# m68k_free_run.net
KiCad netlist of a schematic drawn in EAGLE
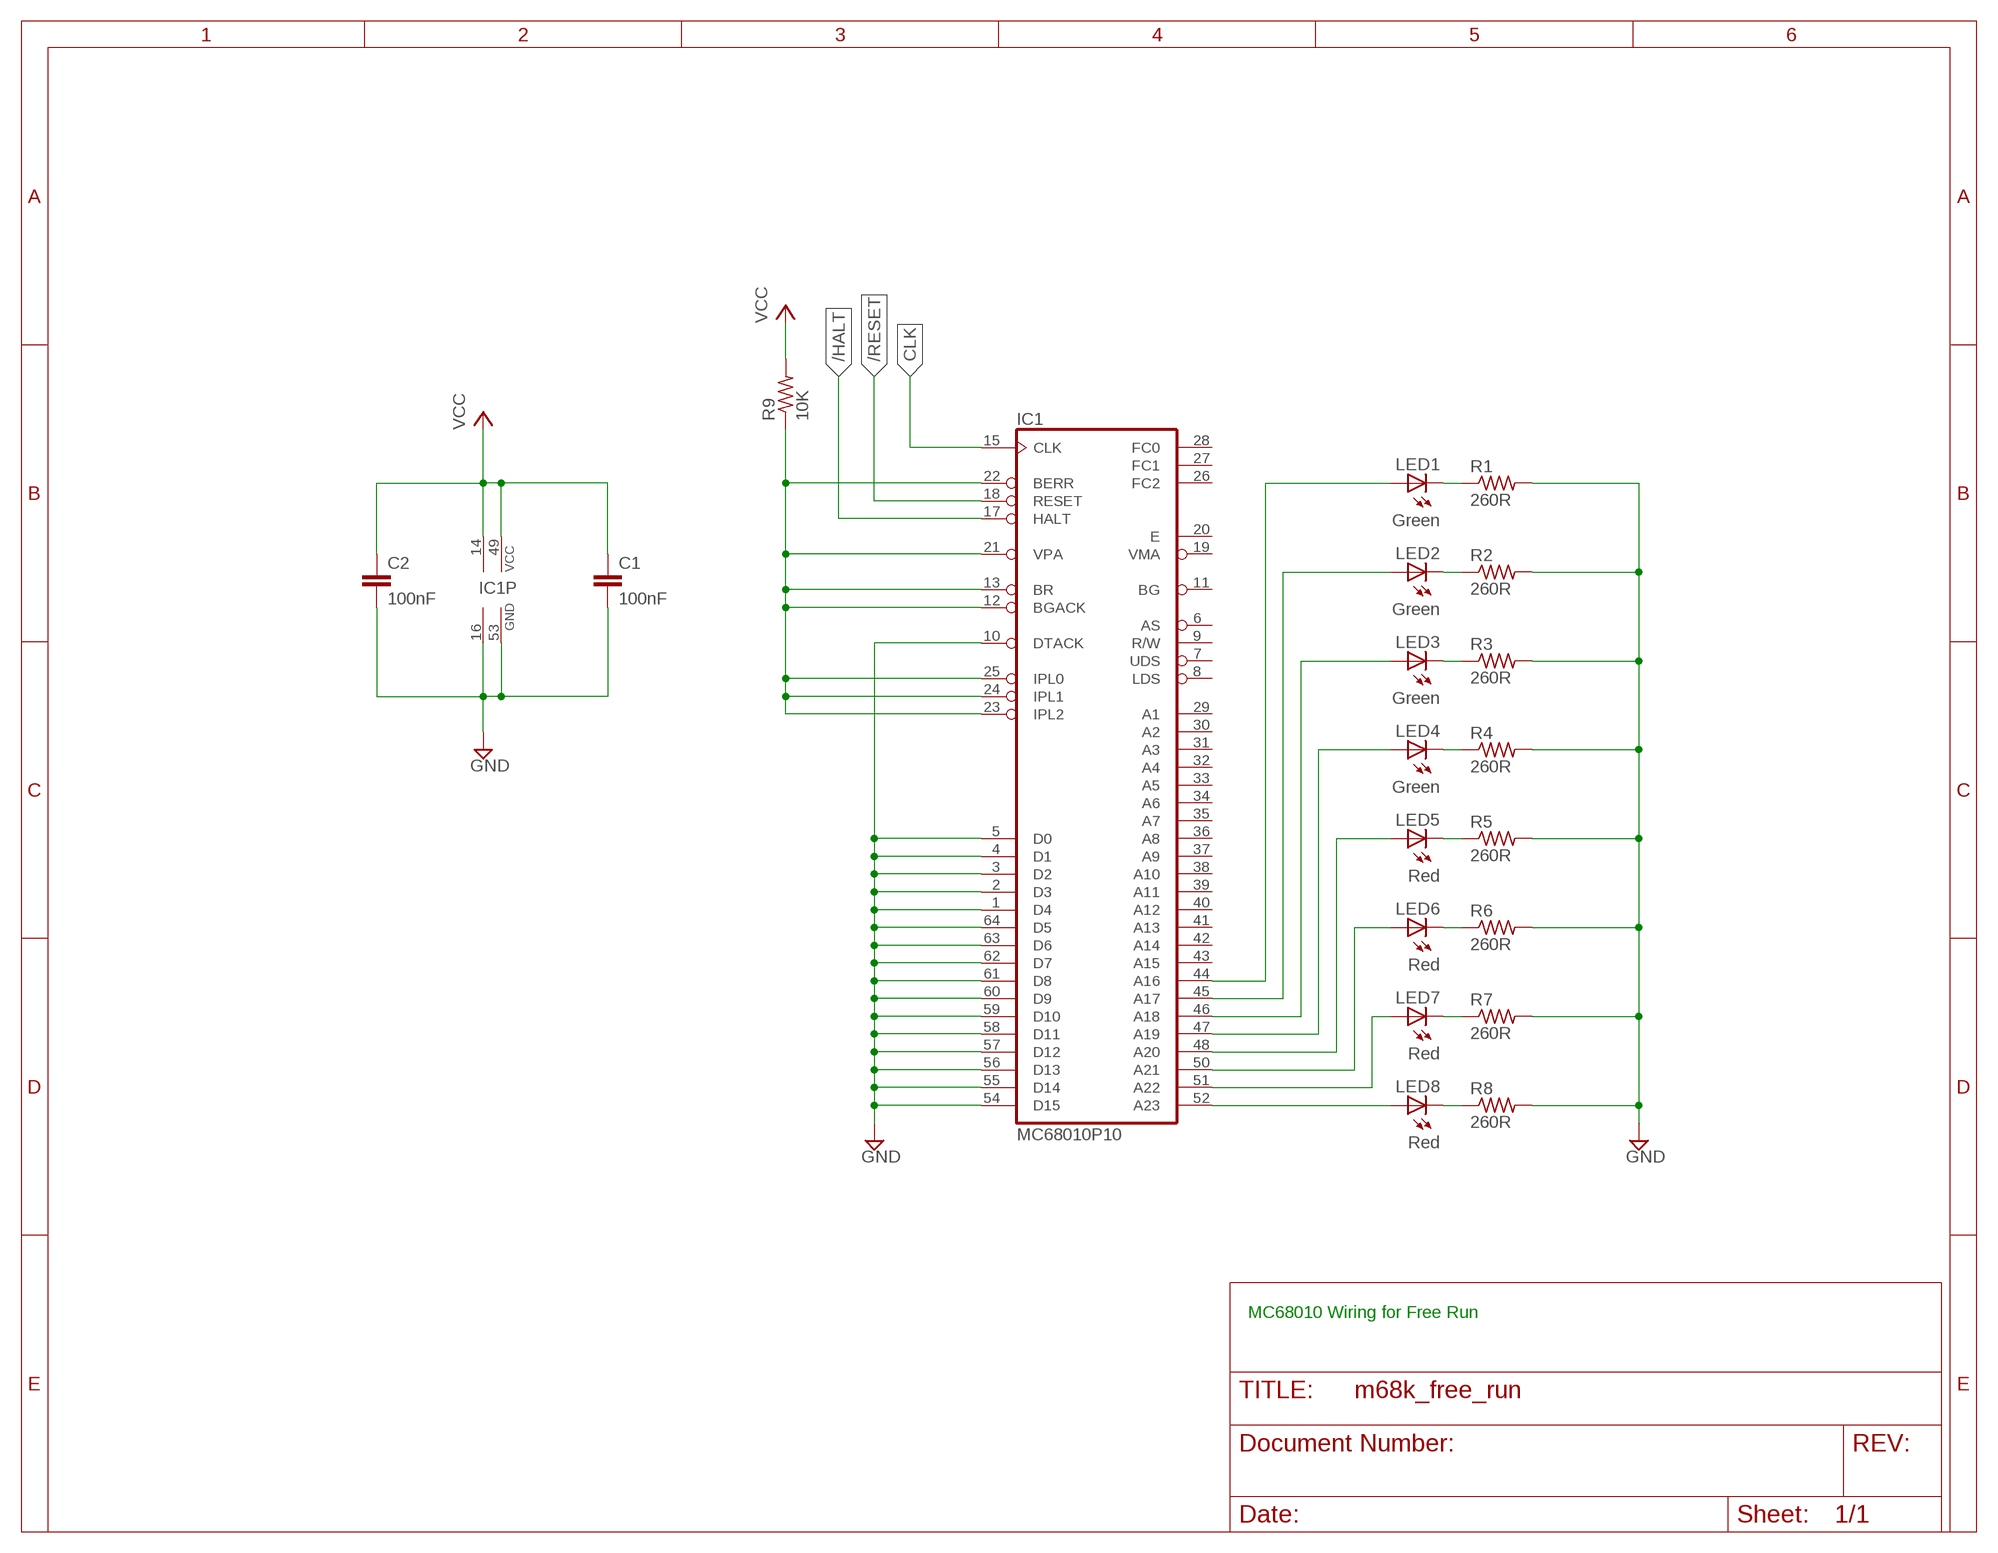
[diagram p0: schematic, sheet 1]

(export (version "E")
  (design (tool "Eeschema 10.0.6"))
  (components
    (comp (ref "C1")
      (value "100nF")
      (footprint "eagle-import:C025-024X044")
      (libsource (lib "eagle-import") (part "C-EU025-024X044"))
    )
    (comp (ref "C2")
      (value "100nF")
      (footprint "eagle-import:C025-024X044")
      (libsource (lib "eagle-import") (part "C-EU025-024X044"))
    )
    (comp (ref "IC1")
      (value "MC68010P10")
      (footprint "eagle-import:DIL64")
      (libsource (lib "eagle-import") (part "MC68000P"))
    )
    (comp (ref "LED1")
      (value "Green")
      (footprint "eagle-import:LED5MM")
      (libsource (lib "eagle-import") (part "LED5MM"))
    )
    (comp (ref "LED2")
      (value "Green")
      (footprint "eagle-import:LED5MM")
      (libsource (lib "eagle-import") (part "LED5MM"))
    )
    (comp (ref "LED3")
      (value "Green")
      (footprint "eagle-import:LED5MM")
      (libsource (lib "eagle-import") (part "LED5MM"))
    )
    (comp (ref "LED4")
      (value "Green")
      (footprint "eagle-import:LED5MM")
      (libsource (lib "eagle-import") (part "LED5MM"))
    )
    (comp (ref "LED5")
      (value "Red")
      (footprint "eagle-import:LED5MM")
      (libsource (lib "eagle-import") (part "LED5MM"))
    )
    (comp (ref "LED6")
      (value "Red")
      (footprint "eagle-import:LED5MM")
      (libsource (lib "eagle-import") (part "LED5MM"))
    )
    (comp (ref "LED7")
      (value "Red")
      (footprint "eagle-import:LED5MM")
      (libsource (lib "eagle-import") (part "LED5MM"))
    )
    (comp (ref "LED8")
      (value "Red")
      (footprint "eagle-import:LED5MM")
      (libsource (lib "eagle-import") (part "LED5MM"))
    )
    (comp (ref "R1")
      (value "260R")
      (footprint "eagle-import:0207_10")
      (libsource (lib "eagle-import") (part "R-US_0207/10"))
    )
    (comp (ref "R2")
      (value "260R")
      (footprint "eagle-import:0207_10")
      (libsource (lib "eagle-import") (part "R-US_0207/10"))
    )
    (comp (ref "R3")
      (value "260R")
      (footprint "eagle-import:0207_10")
      (libsource (lib "eagle-import") (part "R-US_0207/10"))
    )
    (comp (ref "R4")
      (value "260R")
      (footprint "eagle-import:0207_10")
      (libsource (lib "eagle-import") (part "R-US_0207/10"))
    )
    (comp (ref "R5")
      (value "260R")
      (footprint "eagle-import:0207_10")
      (libsource (lib "eagle-import") (part "R-US_0207/10"))
    )
    (comp (ref "R6")
      (value "260R")
      (footprint "eagle-import:0207_10")
      (libsource (lib "eagle-import") (part "R-US_0207/10"))
    )
    (comp (ref "R7")
      (value "260R")
      (footprint "eagle-import:0207_10")
      (libsource (lib "eagle-import") (part "R-US_0207/10"))
    )
    (comp (ref "R8")
      (value "260R")
      (footprint "eagle-import:0207_10")
      (libsource (lib "eagle-import") (part "R-US_0207/10"))
    )
    (comp (ref "R9")
      (value "10K")
      (footprint "eagle-import:0207_10")
      (libsource (lib "eagle-import") (part "R-US_0207/10"))
    )
  )
  (nets
    (net (code "1") (name "CLK") (class "Default")
      (node (ref "IC1") (pin "15") (pinfunction "CLK_15") (pintype "input"))
    )
    (net (code "2") (name "GND") (class "Default")
      (node (ref "C1") (pin "2") (pinfunction "2_2") (pintype "passive"))
      (node (ref "C2") (pin "2") (pinfunction "2_2") (pintype "passive"))
      (node (ref "IC1") (pin "1") (pinfunction "D4_1") (pintype "bidirectional"))
      (node (ref "IC1") (pin "10") (pinfunction "DTACK_10") (pintype "input"))
      (node (ref "IC1") (pin "16") (pinfunction "GND_16") (pintype "power_in"))
      (node (ref "IC1") (pin "2") (pinfunction "D3_2") (pintype "bidirectional"))
      (node (ref "IC1") (pin "3") (pinfunction "D2_3") (pintype "bidirectional"))
      (node (ref "IC1") (pin "4") (pinfunction "D1_4") (pintype "bidirectional"))
      (node (ref "IC1") (pin "5") (pinfunction "D0_5") (pintype "bidirectional"))
      (node (ref "IC1") (pin "53") (pinfunction "GND_53") (pintype "power_in"))
      (node (ref "IC1") (pin "54") (pinfunction "D15_54") (pintype "bidirectional"))
      (node (ref "IC1") (pin "55") (pinfunction "D14_55") (pintype "bidirectional"))
      (node (ref "IC1") (pin "56") (pinfunction "D13_56") (pintype "bidirectional"))
      (node (ref "IC1") (pin "57") (pinfunction "D12_57") (pintype "bidirectional"))
      (node (ref "IC1") (pin "58") (pinfunction "D11_58") (pintype "bidirectional"))
      (node (ref "IC1") (pin "59") (pinfunction "D10_59") (pintype "bidirectional"))
      (node (ref "IC1") (pin "60") (pinfunction "D9_60") (pintype "bidirectional"))
      (node (ref "IC1") (pin "61") (pinfunction "D8_61") (pintype "bidirectional"))
      (node (ref "IC1") (pin "62") (pinfunction "D7_62") (pintype "bidirectional"))
      (node (ref "IC1") (pin "63") (pinfunction "D6_63") (pintype "bidirectional"))
      (node (ref "IC1") (pin "64") (pinfunction "D5_64") (pintype "bidirectional"))
      (node (ref "R1") (pin "2") (pinfunction "2_2") (pintype "passive"))
      (node (ref "R2") (pin "2") (pinfunction "2_2") (pintype "passive"))
      (node (ref "R3") (pin "2") (pinfunction "2_2") (pintype "passive"))
      (node (ref "R4") (pin "2") (pinfunction "2_2") (pintype "passive"))
      (node (ref "R5") (pin "2") (pinfunction "2_2") (pintype "passive"))
      (node (ref "R6") (pin "2") (pinfunction "2_2") (pintype "passive"))
      (node (ref "R7") (pin "2") (pinfunction "2_2") (pintype "passive"))
      (node (ref "R8") (pin "2") (pinfunction "2_2") (pintype "passive"))
    )
    (net (code "3") (name "Net-(IC1A-A16)") (class "Default")
      (node (ref "IC1") (pin "44") (pinfunction "A16_44") (pintype "output"))
      (node (ref "LED1") (pin "A") (pinfunction "A_A") (pintype "passive"))
    )
    (net (code "4") (name "Net-(IC1A-A17)") (class "Default")
      (node (ref "IC1") (pin "45") (pinfunction "A17_45") (pintype "output"))
      (node (ref "LED2") (pin "A") (pinfunction "A_A") (pintype "passive"))
    )
    (net (code "5") (name "Net-(IC1A-A18)") (class "Default")
      (node (ref "IC1") (pin "46") (pinfunction "A18_46") (pintype "output"))
      (node (ref "LED3") (pin "A") (pinfunction "A_A") (pintype "passive"))
    )
    (net (code "6") (name "Net-(IC1A-A19)") (class "Default")
      (node (ref "IC1") (pin "47") (pinfunction "A19_47") (pintype "output"))
      (node (ref "LED4") (pin "A") (pinfunction "A_A") (pintype "passive"))
    )
    (net (code "7") (name "Net-(IC1A-A20)") (class "Default")
      (node (ref "IC1") (pin "48") (pinfunction "A20_48") (pintype "output"))
      (node (ref "LED5") (pin "A") (pinfunction "A_A") (pintype "passive"))
    )
    (net (code "8") (name "Net-(IC1A-A21)") (class "Default")
      (node (ref "IC1") (pin "50") (pinfunction "A21_50") (pintype "output"))
      (node (ref "LED6") (pin "A") (pinfunction "A_A") (pintype "passive"))
    )
    (net (code "9") (name "Net-(IC1A-A22)") (class "Default")
      (node (ref "IC1") (pin "51") (pinfunction "A22_51") (pintype "output"))
      (node (ref "LED7") (pin "A") (pinfunction "A_A") (pintype "passive"))
    )
    (net (code "10") (name "Net-(IC1A-A23)") (class "Default")
      (node (ref "IC1") (pin "52") (pinfunction "A23_52") (pintype "output"))
      (node (ref "LED8") (pin "A") (pinfunction "A_A") (pintype "passive"))
    )
    (net (code "11") (name "Net-(IC1A-BERR)") (class "Default")
      (node (ref "IC1") (pin "12") (pinfunction "BGACK_12") (pintype "input"))
      (node (ref "IC1") (pin "13") (pinfunction "BR_13") (pintype "input"))
      (node (ref "IC1") (pin "21") (pinfunction "VPA_21") (pintype "input"))
      (node (ref "IC1") (pin "22") (pinfunction "BERR_22") (pintype "input"))
      (node (ref "IC1") (pin "23") (pinfunction "IPL2_23") (pintype "input"))
      (node (ref "IC1") (pin "24") (pinfunction "IPL1_24") (pintype "input"))
      (node (ref "IC1") (pin "25") (pinfunction "IPL0_25") (pintype "input"))
      (node (ref "R9") (pin "1") (pinfunction "1_1") (pintype "passive"))
    )
    (net (code "12") (name "Net-(LED1-C)") (class "Default")
      (node (ref "LED1") (pin "K") (pinfunction "C_K") (pintype "passive"))
      (node (ref "R1") (pin "1") (pinfunction "1_1") (pintype "passive"))
    )
    (net (code "13") (name "Net-(LED2-C)") (class "Default")
      (node (ref "LED2") (pin "K") (pinfunction "C_K") (pintype "passive"))
      (node (ref "R2") (pin "1") (pinfunction "1_1") (pintype "passive"))
    )
    (net (code "14") (name "Net-(LED3-C)") (class "Default")
      (node (ref "LED3") (pin "K") (pinfunction "C_K") (pintype "passive"))
      (node (ref "R3") (pin "1") (pinfunction "1_1") (pintype "passive"))
    )
    (net (code "15") (name "Net-(LED4-C)") (class "Default")
      (node (ref "LED4") (pin "K") (pinfunction "C_K") (pintype "passive"))
      (node (ref "R4") (pin "1") (pinfunction "1_1") (pintype "passive"))
    )
    (net (code "16") (name "Net-(LED5-C)") (class "Default")
      (node (ref "LED5") (pin "K") (pinfunction "C_K") (pintype "passive"))
      (node (ref "R5") (pin "1") (pinfunction "1_1") (pintype "passive"))
    )
    (net (code "17") (name "Net-(LED6-C)") (class "Default")
      (node (ref "LED6") (pin "K") (pinfunction "C_K") (pintype "passive"))
      (node (ref "R6") (pin "1") (pinfunction "1_1") (pintype "passive"))
    )
    (net (code "18") (name "Net-(LED7-C)") (class "Default")
      (node (ref "LED7") (pin "K") (pinfunction "C_K") (pintype "passive"))
      (node (ref "R7") (pin "1") (pinfunction "1_1") (pintype "passive"))
    )
    (net (code "19") (name "Net-(LED8-C)") (class "Default")
      (node (ref "LED8") (pin "K") (pinfunction "C_K") (pintype "passive"))
      (node (ref "R8") (pin "1") (pinfunction "1_1") (pintype "passive"))
    )
    (net (code "20") (name "VCC") (class "Default")
      (node (ref "C1") (pin "1") (pinfunction "1_1") (pintype "passive"))
      (node (ref "C2") (pin "1") (pinfunction "1_1") (pintype "passive"))
      (node (ref "IC1") (pin "14") (pinfunction "VCC_14") (pintype "power_in"))
      (node (ref "IC1") (pin "49") (pinfunction "VCC_49") (pintype "power_in"))
      (node (ref "R9") (pin "2") (pinfunction "2_2") (pintype "passive"))
    )
    (net (code "21") (name "unconnected-(IC1A-A1-Pad29)") (class "Default")
      (node (ref "IC1") (pin "29") (pinfunction "A1_29") (pintype "output"))
    )
    (net (code "22") (name "unconnected-(IC1A-A2-Pad30)") (class "Default")
      (node (ref "IC1") (pin "30") (pinfunction "A2_30") (pintype "output"))
    )
    (net (code "23") (name "unconnected-(IC1A-A3-Pad31)") (class "Default")
      (node (ref "IC1") (pin "31") (pinfunction "A3_31") (pintype "output"))
    )
    (net (code "24") (name "unconnected-(IC1A-A4-Pad32)") (class "Default")
      (node (ref "IC1") (pin "32") (pinfunction "A4_32") (pintype "output"))
    )
    (net (code "25") (name "unconnected-(IC1A-A5-Pad33)") (class "Default")
      (node (ref "IC1") (pin "33") (pinfunction "A5_33") (pintype "output"))
    )
    (net (code "26") (name "unconnected-(IC1A-A6-Pad34)") (class "Default")
      (node (ref "IC1") (pin "34") (pinfunction "A6_34") (pintype "output"))
    )
    (net (code "27") (name "unconnected-(IC1A-A7-Pad35)") (class "Default")
      (node (ref "IC1") (pin "35") (pinfunction "A7_35") (pintype "output"))
    )
    (net (code "28") (name "unconnected-(IC1A-A8-Pad36)") (class "Default")
      (node (ref "IC1") (pin "36") (pinfunction "A8_36") (pintype "output"))
    )
    (net (code "29") (name "unconnected-(IC1A-A9-Pad37)") (class "Default")
      (node (ref "IC1") (pin "37") (pinfunction "A9_37") (pintype "output"))
    )
    (net (code "30") (name "unconnected-(IC1A-A10-Pad38)") (class "Default")
      (node (ref "IC1") (pin "38") (pinfunction "A10_38") (pintype "output"))
    )
    (net (code "31") (name "unconnected-(IC1A-A11-Pad39)") (class "Default")
      (node (ref "IC1") (pin "39") (pinfunction "A11_39") (pintype "output"))
    )
    (net (code "32") (name "unconnected-(IC1A-A12-Pad40)") (class "Default")
      (node (ref "IC1") (pin "40") (pinfunction "A12_40") (pintype "output"))
    )
    (net (code "33") (name "unconnected-(IC1A-A13-Pad41)") (class "Default")
      (node (ref "IC1") (pin "41") (pinfunction "A13_41") (pintype "output"))
    )
    (net (code "34") (name "unconnected-(IC1A-A14-Pad42)") (class "Default")
      (node (ref "IC1") (pin "42") (pinfunction "A14_42") (pintype "output"))
    )
    (net (code "35") (name "unconnected-(IC1A-A15-Pad43)") (class "Default")
      (node (ref "IC1") (pin "43") (pinfunction "A15_43") (pintype "output"))
    )
    (net (code "36") (name "unconnected-(IC1A-AS-Pad6)") (class "Default")
      (node (ref "IC1") (pin "6") (pinfunction "AS_6") (pintype "output"))
    )
    (net (code "37") (name "unconnected-(IC1A-BG-Pad11)") (class "Default")
      (node (ref "IC1") (pin "11") (pinfunction "BG_11") (pintype "output"))
    )
    (net (code "38") (name "unconnected-(IC1A-E-Pad20)") (class "Default")
      (node (ref "IC1") (pin "20") (pinfunction "E_20") (pintype "output"))
    )
    (net (code "39") (name "unconnected-(IC1A-FC0-Pad28)") (class "Default")
      (node (ref "IC1") (pin "28") (pinfunction "FC0_28") (pintype "output"))
    )
    (net (code "40") (name "unconnected-(IC1A-FC1-Pad27)") (class "Default")
      (node (ref "IC1") (pin "27") (pinfunction "FC1_27") (pintype "output"))
    )
    (net (code "41") (name "unconnected-(IC1A-FC2-Pad26)") (class "Default")
      (node (ref "IC1") (pin "26") (pinfunction "FC2_26") (pintype "output"))
    )
    (net (code "42") (name "unconnected-(IC1A-LDS-Pad8)") (class "Default")
      (node (ref "IC1") (pin "8") (pinfunction "LDS_8") (pintype "output"))
    )
    (net (code "43") (name "unconnected-(IC1A-R{slash}W-Pad9)") (class "Default")
      (node (ref "IC1") (pin "9") (pinfunction "R/W_9") (pintype "output"))
    )
    (net (code "44") (name "unconnected-(IC1A-UDS-Pad7)") (class "Default")
      (node (ref "IC1") (pin "7") (pinfunction "UDS_7") (pintype "output"))
    )
    (net (code "45") (name "unconnected-(IC1A-VMA-Pad19)") (class "Default")
      (node (ref "IC1") (pin "19") (pinfunction "VMA_19") (pintype "output"))
    )
    (net (code "46") (name "{slash}HALT") (class "Default")
      (node (ref "IC1") (pin "17") (pinfunction "HALT_17") (pintype "bidirectional"))
    )
    (net (code "47") (name "{slash}RESET") (class "Default")
      (node (ref "IC1") (pin "18") (pinfunction "RESET_18") (pintype "bidirectional"))
    )
  )
)
